# R_le_Mod_l_ift.net
KiCad netlist of a schematic drawn in EAGLE
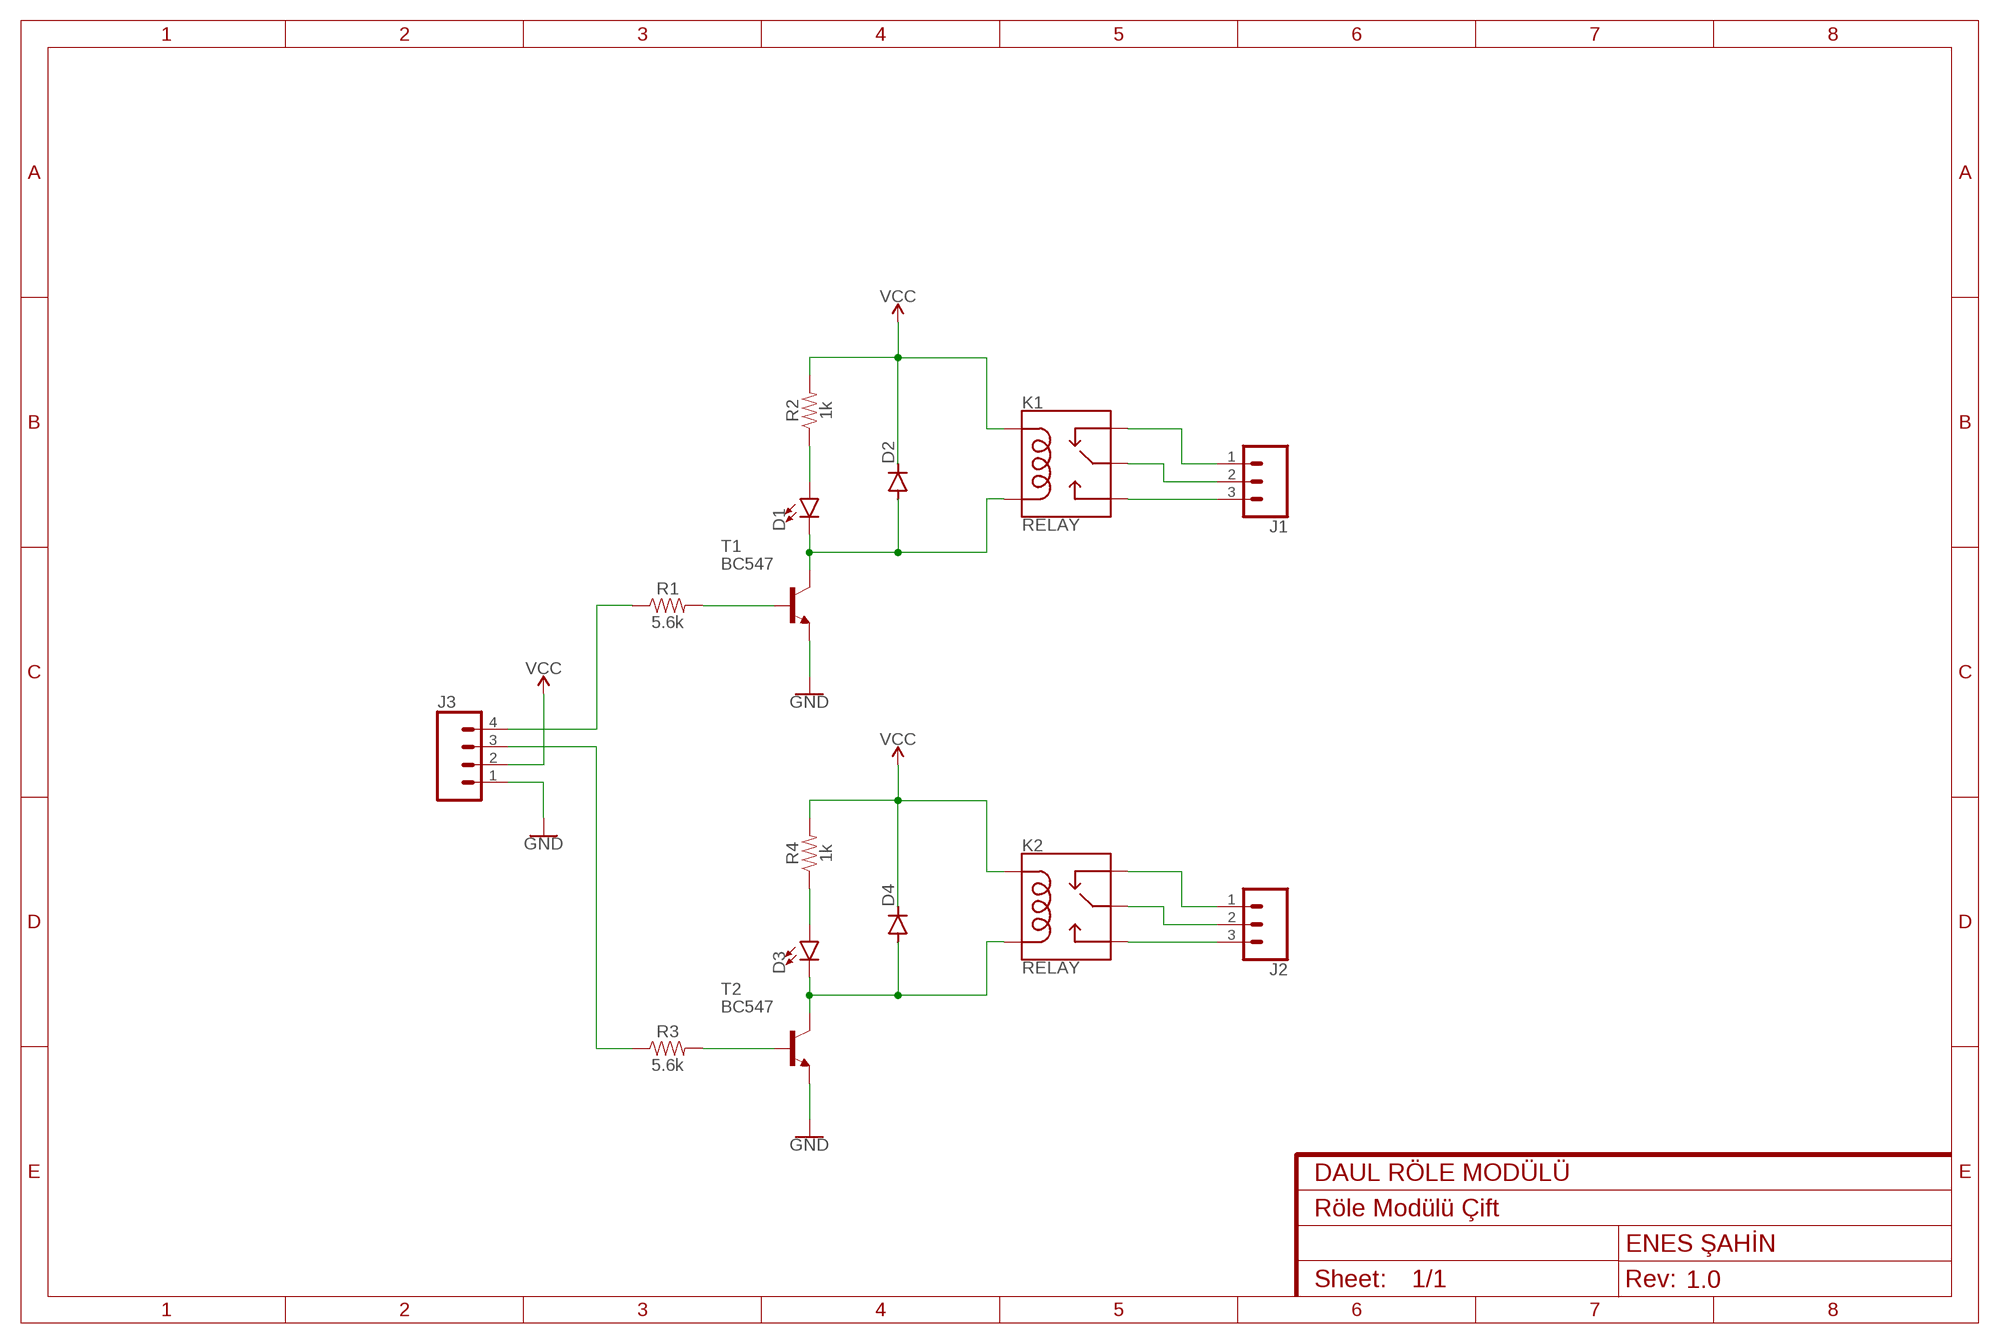
[diagram p0: schematic, sheet 1]

(export (version "E")
  (design (tool "Eeschema 10.0.6"))
  (components
    (comp (ref "D1")
      (value "LED3MM")
      (footprint "eagle-import:LED_3MM")
      (libsource (lib "eagle-import") (part "LED3MM"))
    )
    (comp (ref "D2")
      (value "DIODE-DO07")
      (footprint "eagle-import:DO07")
      (libsource (lib "eagle-import") (part "DIODE-DO07"))
    )
    (comp (ref "D3")
      (value "LED3MM")
      (footprint "eagle-import:LED_3MM")
      (libsource (lib "eagle-import") (part "LED3MM"))
    )
    (comp (ref "D4")
      (value "DIODE-DO07")
      (footprint "eagle-import:DO07")
      (libsource (lib "eagle-import") (part "DIODE-DO07"))
    )
    (comp (ref "J1")
      (value "CONN_03")
      (footprint "eagle-import:1X03")
      (libsource (lib "eagle-import") (part "CONN_03"))
    )
    (comp (ref "J2")
      (value "CONN_03")
      (footprint "eagle-import:1X03")
      (libsource (lib "eagle-import") (part "CONN_03"))
    )
    (comp (ref "J3")
      (value "CONN_04")
      (footprint "eagle-import:1X04")
      (libsource (lib "eagle-import") (part "CONN_04"))
    )
    (comp (ref "K1")
      (value "RELAY")
      (footprint "eagle-import:RELAY-JZC")
      (libsource (lib "eagle-import") (part "RELAY-SPDT-JZC-11F"))
    )
    (comp (ref "K2")
      (value "RELAY")
      (footprint "eagle-import:RELAY-JZC")
      (libsource (lib "eagle-import") (part "RELAY-SPDT-JZC-11F"))
    )
    (comp (ref "R1")
      (value "5.6k")
      (footprint "eagle-import:AXIAL-0.3")
      (libsource (lib "eagle-import") (part "1KOHM-HORIZ-1/4W-1%"))
    )
    (comp (ref "R2")
      (value "1k")
      (footprint "eagle-import:AXIAL-0.3")
      (libsource (lib "eagle-import") (part "1KOHM-HORIZ-1/4W-1%"))
    )
    (comp (ref "R3")
      (value "5.6k")
      (footprint "eagle-import:AXIAL-0.3")
      (libsource (lib "eagle-import") (part "1KOHM-HORIZ-1/4W-1%"))
    )
    (comp (ref "R4")
      (value "1k")
      (footprint "eagle-import:AXIAL-0.3")
      (libsource (lib "eagle-import") (part "1KOHM-HORIZ-1/4W-1%"))
    )
    (comp (ref "T1")
      (value "BC547")
      (footprint "eagle-import:TO92")
      (libsource (lib "eagle-import") (part "BC547"))
    )
    (comp (ref "T2")
      (value "BC547")
      (footprint "eagle-import:TO92")
      (libsource (lib "eagle-import") (part "BC547"))
    )
  )
  (nets
    (net (code "1") (name "GND") (class "Default")
      (node (ref "J3") (pin "1") (pinfunction "1_1") (pintype "passive"))
      (node (ref "T1") (pin "1") (pinfunction "E_1") (pintype "passive"))
      (node (ref "T2") (pin "1") (pinfunction "E_1") (pintype "passive"))
    )
    (net (code "2") (name "Net-(D1-C)") (class "Default")
      (node (ref "D1") (pin "K") (pinfunction "C_K") (pintype "passive"))
      (node (ref "D2") (pin "A") (pinfunction "A_A") (pintype "passive"))
      (node (ref "K1") (pin "1") (pinfunction "COIL2_1") (pintype "bidirectional"))
      (node (ref "T1") (pin "3") (pinfunction "C_3") (pintype "passive"))
    )
    (net (code "3") (name "Net-(D3-C)") (class "Default")
      (node (ref "D3") (pin "K") (pinfunction "C_K") (pintype "passive"))
      (node (ref "D4") (pin "A") (pinfunction "A_A") (pintype "passive"))
      (node (ref "K2") (pin "1") (pinfunction "COIL2_1") (pintype "bidirectional"))
      (node (ref "T2") (pin "3") (pinfunction "C_3") (pintype "passive"))
    )
    (net (code "4") (name "Net-(K1-MAIN)") (class "Default")
      (node (ref "J1") (pin "2") (pinfunction "2_2") (pintype "passive"))
      (node (ref "K1") (pin "4") (pinfunction "MAIN_4") (pintype "bidirectional"))
    )
    (net (code "5") (name "Net-(K1-NC)") (class "Default")
      (node (ref "J1") (pin "1") (pinfunction "1_1") (pintype "passive"))
      (node (ref "K1") (pin "2") (pinfunction "NC_2") (pintype "bidirectional"))
    )
    (net (code "6") (name "Net-(K1-NO)") (class "Default")
      (node (ref "J1") (pin "3") (pinfunction "3_3") (pintype "passive"))
      (node (ref "K1") (pin "3") (pinfunction "NO_3") (pintype "bidirectional"))
    )
    (net (code "7") (name "Net-(K2-MAIN)") (class "Default")
      (node (ref "J2") (pin "2") (pinfunction "2_2") (pintype "passive"))
      (node (ref "K2") (pin "4") (pinfunction "MAIN_4") (pintype "bidirectional"))
    )
    (net (code "8") (name "Net-(K2-NC)") (class "Default")
      (node (ref "J2") (pin "1") (pinfunction "1_1") (pintype "passive"))
      (node (ref "K2") (pin "2") (pinfunction "NC_2") (pintype "bidirectional"))
    )
    (net (code "9") (name "Net-(K2-NO)") (class "Default")
      (node (ref "J2") (pin "3") (pinfunction "3_3") (pintype "passive"))
      (node (ref "K2") (pin "3") (pinfunction "NO_3") (pintype "bidirectional"))
    )
    (net (code "10") (name "Net-(R1-1)") (class "Default")
      (node (ref "J3") (pin "4") (pinfunction "4_4") (pintype "passive"))
      (node (ref "R1") (pin "P$1") (pinfunction "1_P$1") (pintype "passive"))
    )
    (net (code "11") (name "Net-(R1-2)") (class "Default")
      (node (ref "R1") (pin "P$2") (pinfunction "2_P$2") (pintype "passive"))
      (node (ref "T1") (pin "2") (pinfunction "B_2") (pintype "passive"))
    )
    (net (code "12") (name "Net-(R2-1)") (class "Default")
      (node (ref "D1") (pin "A") (pinfunction "A_A") (pintype "passive"))
      (node (ref "R2") (pin "P$1") (pinfunction "1_P$1") (pintype "passive"))
    )
    (net (code "13") (name "Net-(R3-1)") (class "Default")
      (node (ref "J3") (pin "3") (pinfunction "3_3") (pintype "passive"))
      (node (ref "R3") (pin "P$1") (pinfunction "1_P$1") (pintype "passive"))
    )
    (net (code "14") (name "Net-(R3-2)") (class "Default")
      (node (ref "R3") (pin "P$2") (pinfunction "2_P$2") (pintype "passive"))
      (node (ref "T2") (pin "2") (pinfunction "B_2") (pintype "passive"))
    )
    (net (code "15") (name "Net-(R4-1)") (class "Default")
      (node (ref "D3") (pin "A") (pinfunction "A_A") (pintype "passive"))
      (node (ref "R4") (pin "P$1") (pinfunction "1_P$1") (pintype "passive"))
    )
    (net (code "16") (name "VCC") (class "Default")
      (node (ref "D2") (pin "C") (pinfunction "C_C") (pintype "passive"))
      (node (ref "D4") (pin "C") (pinfunction "C_C") (pintype "passive"))
      (node (ref "J3") (pin "2") (pinfunction "2_2") (pintype "passive"))
      (node (ref "K1") (pin "5") (pinfunction "COIL1_5") (pintype "bidirectional"))
      (node (ref "K2") (pin "5") (pinfunction "COIL1_5") (pintype "bidirectional"))
      (node (ref "R2") (pin "P$2") (pinfunction "2_P$2") (pintype "passive"))
      (node (ref "R4") (pin "P$2") (pinfunction "2_P$2") (pintype "passive"))
    )
  )
)
